# USB_to_DB9.net
KiCad netlist of a schematic drawn in Altium Designer
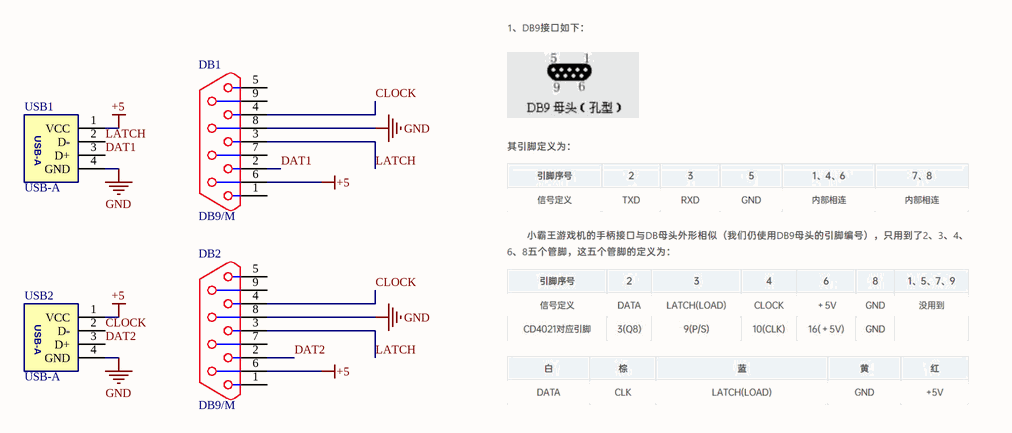
[diagram p0: USB to DB9.SchDoc]

(export (version "E")
  (design (tool "Eeschema 10.0.6"))
  (components
    (comp (ref "DB1") (value "DB9/M") (footprint "DB9/M/90") (libsource (lib "通讯类-串口") (part "DB9/M")))
    (comp (ref "DB2") (value "DB9/M") (footprint "DB9/M/90") (libsource (lib "通讯类-串口") (part "DB9/M")))
    (comp (ref "USB1") (value "USB-A") (footprint "USB_A/P_A") (libsource (lib "插座-USB连接器") (part "USB-A")))
    (comp (ref "USB2") (value "USB-A") (footprint "USB_A/P_A") (libsource (lib "插座-USB连接器") (part "USB-A")))
  )
  (nets
    (net (code "1") (name "+5") (class "Default")
      (node (ref "DB1") (pin "6") (pinfunction "6_6") (pintype "passive"))
      (node (ref "DB2") (pin "6") (pinfunction "6_6") (pintype "passive"))
      (node (ref "USB1") (pin "1") (pinfunction "VCC_1") (pintype "passive"))
      (node (ref "USB2") (pin "1") (pinfunction "VCC_1") (pintype "passive"))
    )
    (net (code "2") (name "/CLOCK") (class "Default")
      (node (ref "DB1") (pin "4") (pinfunction "4_4") (pintype "passive"))
      (node (ref "DB2") (pin "4") (pinfunction "4_4") (pintype "passive"))
      (node (ref "USB2") (pin "2") (pinfunction "D-_2") (pintype "passive"))
    )
    (net (code "3") (name "/DAT1") (class "Default")
      (node (ref "DB1") (pin "2") (pinfunction "2_2") (pintype "passive"))
      (node (ref "USB1") (pin "3") (pinfunction "D+_3") (pintype "passive"))
    )
    (net (code "4") (name "/DAT2") (class "Default")
      (node (ref "DB2") (pin "2") (pinfunction "2_2") (pintype "passive"))
      (node (ref "USB2") (pin "3") (pinfunction "D+_3") (pintype "passive"))
    )
    (net (code "5") (name "/LATCH") (class "Default")
      (node (ref "DB1") (pin "3") (pinfunction "3_3") (pintype "passive"))
      (node (ref "DB2") (pin "3") (pinfunction "3_3") (pintype "passive"))
      (node (ref "USB1") (pin "2") (pinfunction "D-_2") (pintype "passive"))
    )
    (net (code "6") (name "GND") (class "Default")
      (node (ref "DB1") (pin "8") (pinfunction "8_8") (pintype "passive"))
      (node (ref "DB2") (pin "8") (pinfunction "8_8") (pintype "passive"))
      (node (ref "USB1") (pin "4") (pinfunction "GND_4") (pintype "passive"))
      (node (ref "USB2") (pin "4") (pinfunction "GND_4") (pintype "passive"))
    )
    (net (code "7") (name "unconnected-(DB1-Pad1)") (class "Default")
      (node (ref "DB1") (pin "1") (pinfunction "1_1") (pintype "passive"))
    )
    (net (code "8") (name "unconnected-(DB1-Pad5)") (class "Default")
      (node (ref "DB1") (pin "5") (pinfunction "5_5") (pintype "passive"))
    )
    (net (code "9") (name "unconnected-(DB1-Pad7)") (class "Default")
      (node (ref "DB1") (pin "7") (pinfunction "7_7") (pintype "passive"))
    )
    (net (code "10") (name "unconnected-(DB1-Pad9)") (class "Default")
      (node (ref "DB1") (pin "9") (pinfunction "9_9") (pintype "passive"))
    )
    (net (code "11") (name "unconnected-(DB2-Pad1)") (class "Default")
      (node (ref "DB2") (pin "1") (pinfunction "1_1") (pintype "passive"))
    )
    (net (code "12") (name "unconnected-(DB2-Pad5)") (class "Default")
      (node (ref "DB2") (pin "5") (pinfunction "5_5") (pintype "passive"))
    )
    (net (code "13") (name "unconnected-(DB2-Pad7)") (class "Default")
      (node (ref "DB2") (pin "7") (pinfunction "7_7") (pintype "passive"))
    )
    (net (code "14") (name "unconnected-(DB2-Pad9)") (class "Default")
      (node (ref "DB2") (pin "9") (pinfunction "9_9") (pintype "passive"))
    )
  )
)
